# CurrentAmp.net
KiCad netlist of a schematic drawn in EAGLE
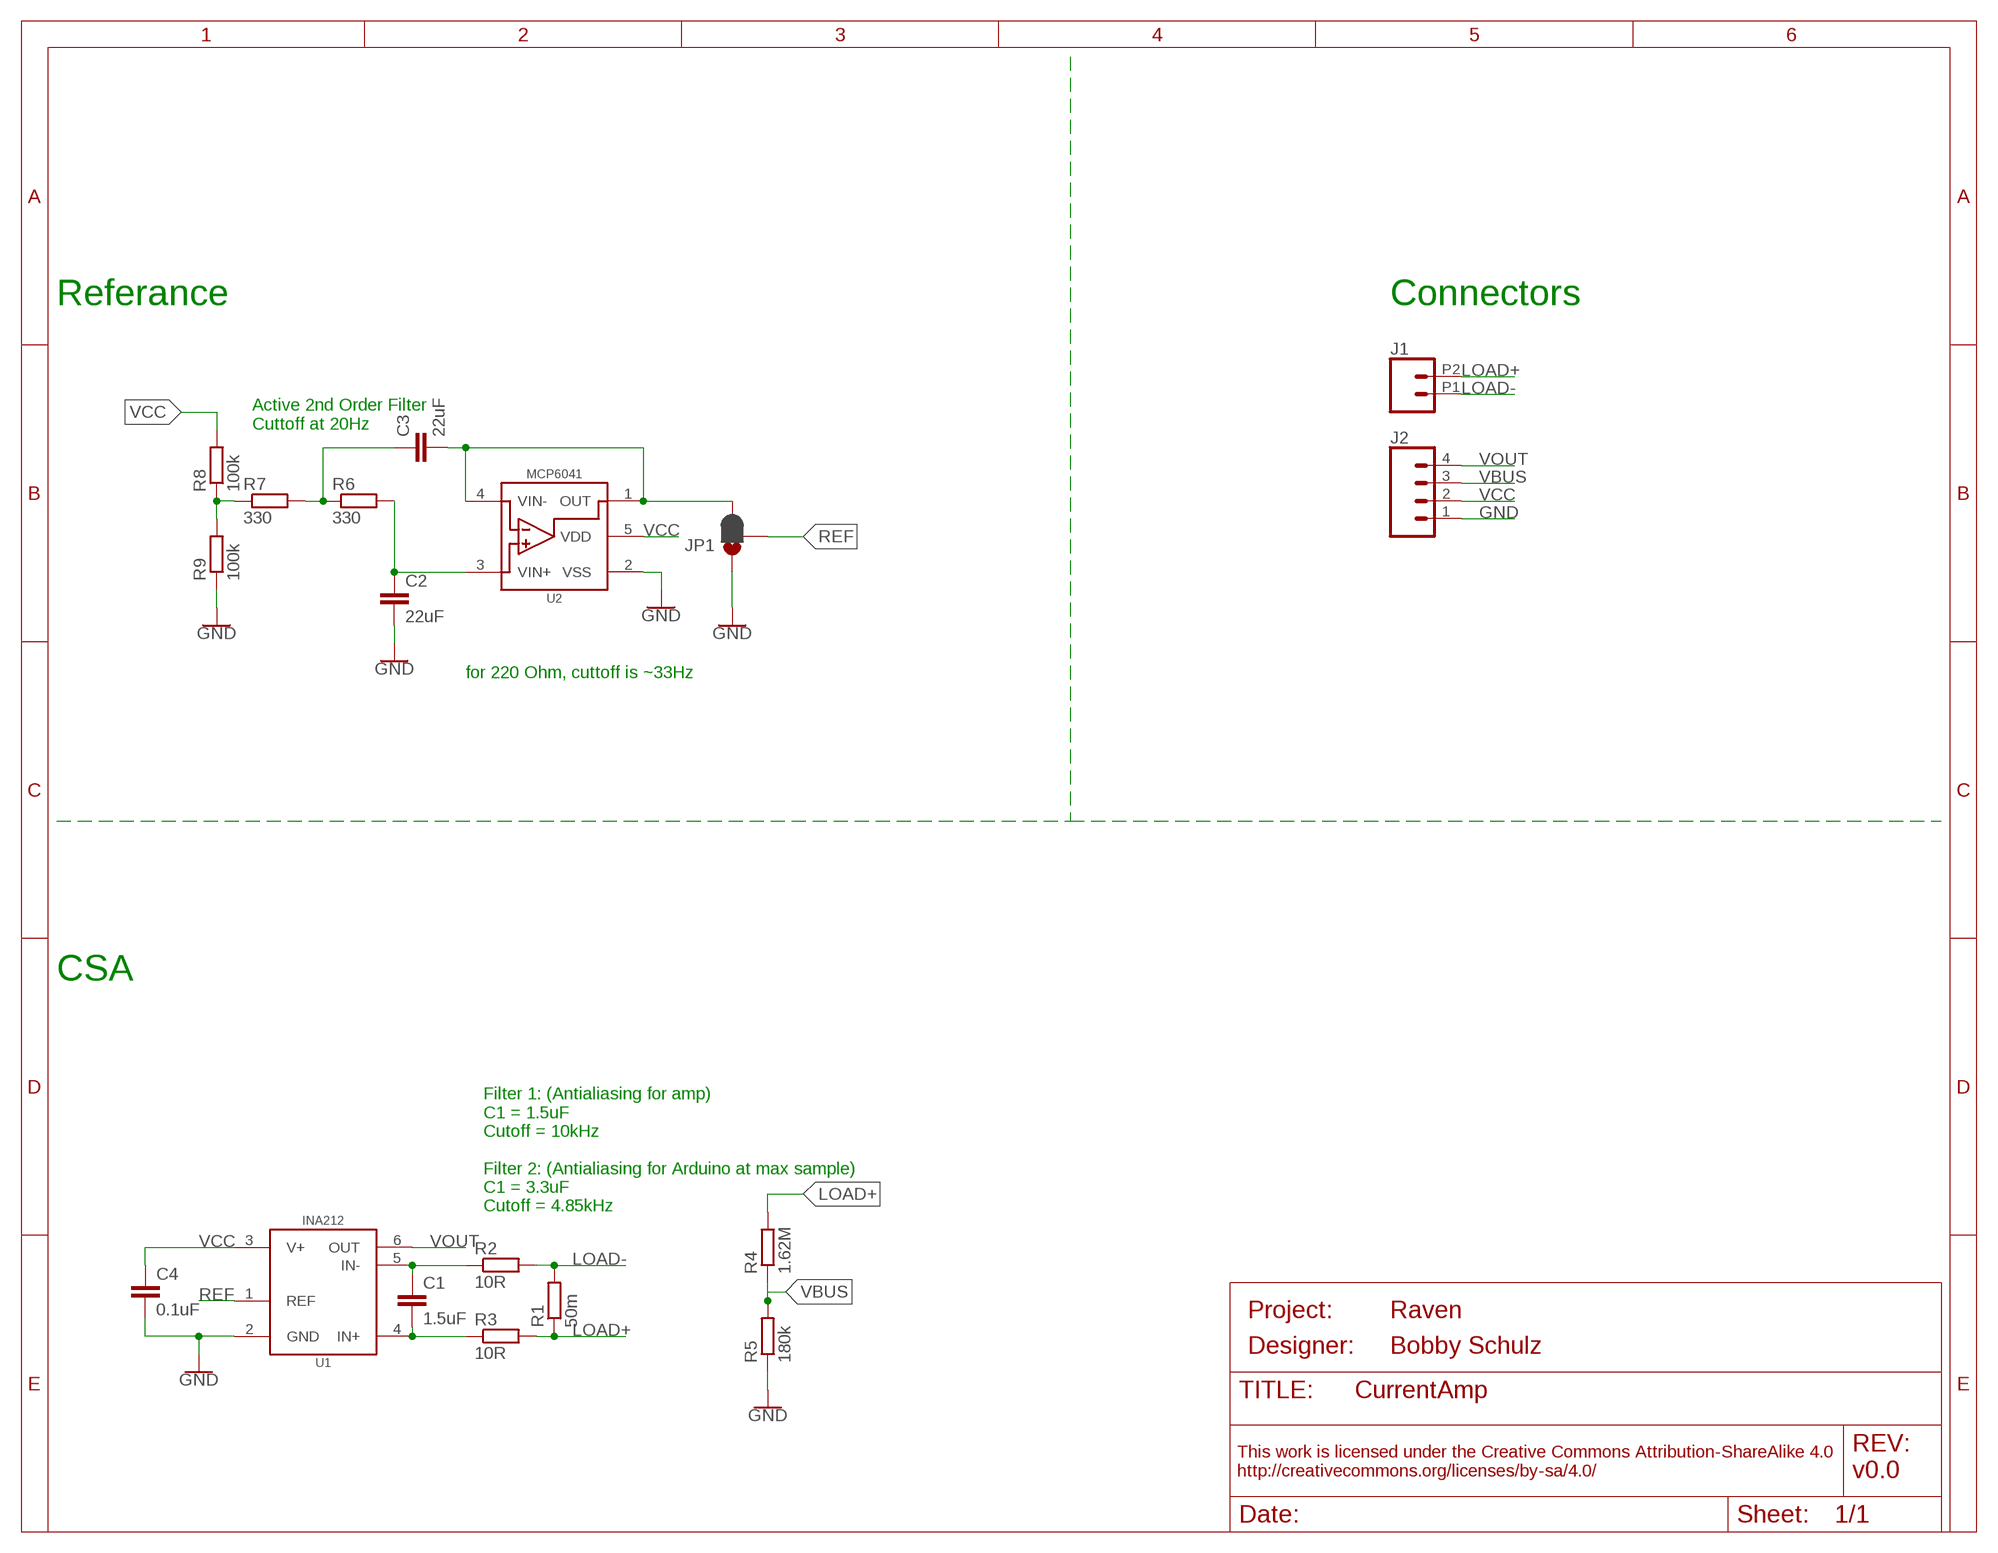
[diagram p0: schematic, sheet 1]

(export (version "E")
  (design (tool "Eeschema 10.0.6"))
  (components
    (comp (ref "C1")
      (value "1.5uF")
      (footprint "eagle-import:C0603")
      (libsource (lib "eagle-import") (part "C-EUC0603"))
    )
    (comp (ref "C2")
      (value "22uF")
      (footprint "eagle-import:C0805")
      (libsource (lib "eagle-import") (part "C-EUC0805"))
    )
    (comp (ref "C3")
      (value "22uF")
      (footprint "eagle-import:C0805")
      (libsource (lib "eagle-import") (part "C-EUC0805"))
    )
    (comp (ref "C4")
      (value "0.1uF")
      (footprint "eagle-import:C0603")
      (libsource (lib "eagle-import") (part "C-EUC0603"))
    )
    (comp (ref "J1")
      (value "CONN_022.54MM_SCREWTERM")
      (footprint "eagle-import:1X02_2.54_SCREWTERM")
      (libsource (lib "eagle-import") (part "CONN_022.54MM_SCREWTERM"))
    )
    (comp (ref "J2")
      (value "CONN_42.54_SCREW")
      (footprint "eagle-import:1X04_SCREW")
      (fields (field (name "MF") "On Shore") (field (name "MPN") "OSTVN04A150"))
      (libsource (lib "eagle-import") (part "CONN_42.54_SCREW"))
    )
    (comp (ref "JP1")
      (value "JUMPER-SMT_3_1-NC_PASTE_SILK")
      (footprint "eagle-import:SMT-JUMPER_3_1-NC_PASTE_SILK")
      (libsource (lib "eagle-import") (part "JUMPER-SMT_3_1-NC_PASTE_SILK"))
    )
    (comp (ref "R1")
      (value "50m")
      (footprint "eagle-import:R0805")
      (libsource (lib "eagle-import") (part "R-EU_R0805"))
    )
    (comp (ref "R2")
      (value "10R")
      (footprint "eagle-import:R0603")
      (fields (field (name "MF") "Yageo"))
      (libsource (lib "eagle-import") (part "R-EU_R0603"))
    )
    (comp (ref "R3")
      (value "10R")
      (footprint "eagle-import:R0603")
      (fields (field (name "MF") "Yageo"))
      (libsource (lib "eagle-import") (part "R-EU_R0603"))
    )
    (comp (ref "R4")
      (value "1.62M")
      (footprint "eagle-import:R0603")
      (fields (field (name "MF") "Yageo"))
      (libsource (lib "eagle-import") (part "R-EU_R0603"))
    )
    (comp (ref "R5")
      (value "180k")
      (footprint "eagle-import:R0603")
      (fields (field (name "MF") "Yageo"))
      (libsource (lib "eagle-import") (part "R-EU_R0603"))
    )
    (comp (ref "R6")
      (value "330")
      (footprint "eagle-import:R0603")
      (fields (field (name "MF") "Yageo"))
      (libsource (lib "eagle-import") (part "R-EU_R0603"))
    )
    (comp (ref "R7")
      (value "330")
      (footprint "eagle-import:R0603")
      (fields (field (name "MF") "Yageo"))
      (libsource (lib "eagle-import") (part "R-EU_R0603"))
    )
    (comp (ref "R8")
      (value "100k")
      (footprint "eagle-import:R0603")
      (fields (field (name "MF") "Yageo"))
      (libsource (lib "eagle-import") (part "R-EU_R0603"))
    )
    (comp (ref "R9")
      (value "100k")
      (footprint "eagle-import:R0603")
      (fields (field (name "MF") "Yageo"))
      (libsource (lib "eagle-import") (part "R-EU_R0603"))
    )
    (comp (ref "U1")
      (value "INA212DCK")
      (footprint "eagle-import:DCK_R-PDSO-G6")
      (fields (field (name "DISP") "INA212") (field (name "MF") "TI") (field (name "MPN") "INA212BIDCKR"))
      (libsource (lib "eagle-import") (part "INA21DCK2"))
    )
    (comp (ref "U2")
      (value "MCP6041")
      (footprint "eagle-import:SOT23-5")
      (fields
        (field (name "DISP") "MCP6041")
        (field (name "MF") "Microchip")
        (field (name "MPN") "MCP6041T-I/OT")
      )
      (libsource (lib "eagle-import") (part "MCP6041"))
    )
  )
  (nets
    (net (code "1") (name "/LOAD-") (class "Default")
      (node (ref "J1") (pin "P1") (pinfunction "1_P1") (pintype "passive"))
      (node (ref "R1") (pin "2") (pinfunction "2_2") (pintype "passive"))
      (node (ref "R2") (pin "2") (pinfunction "2_2") (pintype "passive"))
    )
    (net (code "2") (name "/VOUT") (class "Default")
      (node (ref "J2") (pin "4") (pinfunction "4_4") (pintype "passive"))
      (node (ref "U1") (pin "6") (pinfunction "OUT_6") (pintype "bidirectional"))
    )
    (net (code "3") (name "GND") (class "Default")
      (node (ref "C2") (pin "2") (pinfunction "2_2") (pintype "passive"))
      (node (ref "C4") (pin "2") (pinfunction "2_2") (pintype "passive"))
      (node (ref "J2") (pin "1") (pinfunction "1_1") (pintype "passive"))
      (node (ref "JP1") (pin "1") (pinfunction "1_1") (pintype "passive"))
      (node (ref "R5") (pin "1") (pinfunction "1_1") (pintype "passive"))
      (node (ref "R9") (pin "1") (pinfunction "1_1") (pintype "passive"))
      (node (ref "U1") (pin "2") (pinfunction "GND_2") (pintype "bidirectional"))
      (node (ref "U2") (pin "2") (pinfunction "VSS_2") (pintype "power_in"))
    )
    (net (code "4") (name "LOAD+") (class "Default")
      (node (ref "J1") (pin "P2") (pinfunction "2_P2") (pintype "passive"))
      (node (ref "R1") (pin "1") (pinfunction "1_1") (pintype "passive"))
      (node (ref "R3") (pin "2") (pinfunction "2_2") (pintype "passive"))
      (node (ref "R4") (pin "2") (pinfunction "2_2") (pintype "passive"))
    )
    (net (code "5") (name "Net-(C3-Pad1)") (class "Default")
      (node (ref "C3") (pin "1") (pinfunction "1_1") (pintype "passive"))
      (node (ref "R6") (pin "1") (pinfunction "1_1") (pintype "passive"))
      (node (ref "R7") (pin "2") (pinfunction "2_2") (pintype "passive"))
    )
    (net (code "6") (name "Net-(R7-Pad1)") (class "Default")
      (node (ref "R7") (pin "1") (pinfunction "1_1") (pintype "passive"))
      (node (ref "R8") (pin "1") (pinfunction "1_1") (pintype "passive"))
      (node (ref "R9") (pin "2") (pinfunction "2_2") (pintype "passive"))
    )
    (net (code "7") (name "Net-(U1-IN+)") (class "Default")
      (node (ref "C1") (pin "2") (pinfunction "2_2") (pintype "passive"))
      (node (ref "R3") (pin "1") (pinfunction "1_1") (pintype "passive"))
      (node (ref "U1") (pin "4") (pinfunction "IN+_4") (pintype "bidirectional"))
    )
    (net (code "8") (name "Net-(U1-IN-)") (class "Default")
      (node (ref "C1") (pin "1") (pinfunction "1_1") (pintype "passive"))
      (node (ref "R2") (pin "1") (pinfunction "1_1") (pintype "passive"))
      (node (ref "U1") (pin "5") (pinfunction "IN-_5") (pintype "bidirectional"))
    )
    (net (code "9") (name "Net-(U2-OUT)") (class "Default")
      (node (ref "C3") (pin "2") (pinfunction "2_2") (pintype "passive"))
      (node (ref "JP1") (pin "3") (pinfunction "3_3") (pintype "passive"))
      (node (ref "U2") (pin "1") (pinfunction "OUT_1") (pintype "output"))
      (node (ref "U2") (pin "4") (pinfunction "VIN-_4") (pintype "input"))
    )
    (net (code "10") (name "Net-(U2-VIN+)") (class "Default")
      (node (ref "C2") (pin "1") (pinfunction "1_1") (pintype "passive"))
      (node (ref "R6") (pin "2") (pinfunction "2_2") (pintype "passive"))
      (node (ref "U2") (pin "3") (pinfunction "VIN+_3") (pintype "input"))
    )
    (net (code "11") (name "REF") (class "Default")
      (node (ref "JP1") (pin "2") (pinfunction "2_2") (pintype "passive"))
      (node (ref "U1") (pin "1") (pinfunction "REF_1") (pintype "bidirectional"))
    )
    (net (code "12") (name "VBUS") (class "Default")
      (node (ref "J2") (pin "3") (pinfunction "3_3") (pintype "passive"))
      (node (ref "R4") (pin "1") (pinfunction "1_1") (pintype "passive"))
      (node (ref "R5") (pin "2") (pinfunction "2_2") (pintype "passive"))
    )
    (net (code "13") (name "VCC") (class "Default")
      (node (ref "C4") (pin "1") (pinfunction "1_1") (pintype "passive"))
      (node (ref "J2") (pin "2") (pinfunction "2_2") (pintype "passive"))
      (node (ref "R8") (pin "2") (pinfunction "2_2") (pintype "passive"))
      (node (ref "U1") (pin "3") (pinfunction "V+_3") (pintype "bidirectional"))
      (node (ref "U2") (pin "5") (pinfunction "VDD_5") (pintype "power_in"))
    )
  )
)
